# ProPrj___2025-12-12.net
KiCad netlist of a schematic drawn in EasyEDA Pro
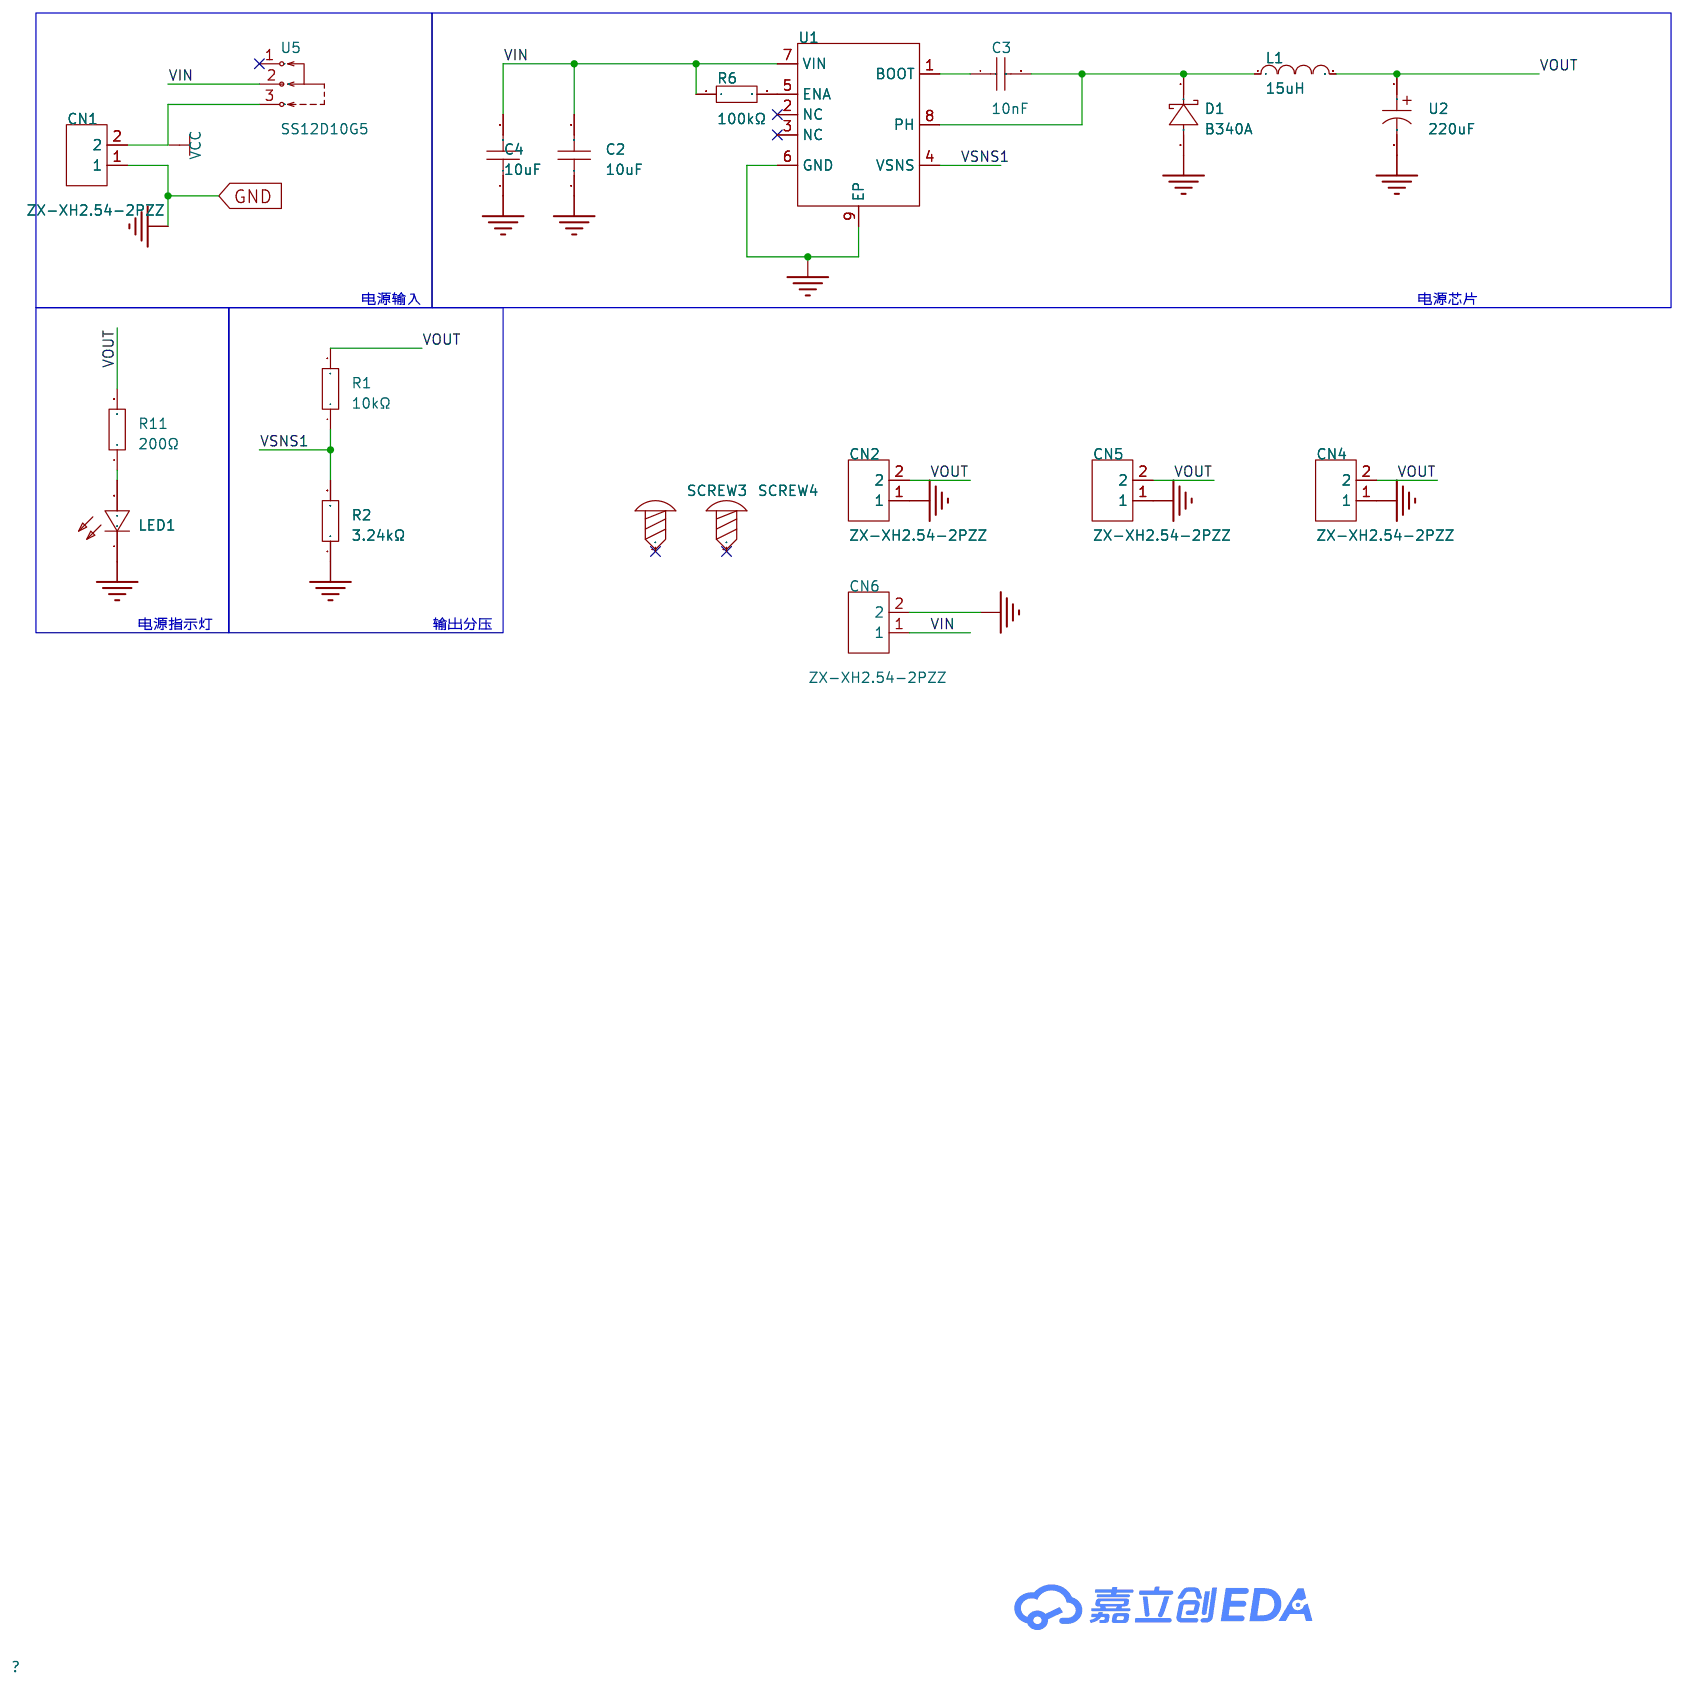
[diagram p0: schematic sheet]

(export (version "E")
  (design (tool "Eeschema 10.0.6"))
  (components
    (comp (ref "C2")
      (value "10uF")
      (footprint "easyedapro:C0603")
      (description "容值:10uF;精度:±20%;额定电压:25V;材质(温度系数):X5R;")
      (fields
        (field (name "Manufacturer Part") "CL10A106MA8NRNC")
        (field (name "Manufacturer") "SAMSUNG(三星)")
      )
      (libsource (lib "easyedapro") (part "CL10A106MA8NRNC"))
    )
    (comp (ref "C3")
      (value "10nF")
      (footprint "easyedapro:C0603")
      (description "容值:10nF;精度:±10%;额定电压:50V;材质(温度系数):X7R;")
      (fields
        (field (name "Manufacturer Part") "CC0603KRX7R9BB103")
        (field (name "Manufacturer") "YAGEO(国巨)")
      )
      (libsource (lib "easyedapro") (part "CC0603KRX7R9BB103"))
    )
    (comp (ref "C4")
      (value "10uF")
      (footprint "easyedapro:C0603")
      (description "容值:10uF;精度:±20%;额定电压:25V;材质(温度系数):X5R;")
      (fields
        (field (name "Manufacturer Part") "CL10A106MA8NRNC")
        (field (name "Manufacturer") "SAMSUNG(三星)")
      )
      (libsource (lib "easyedapro") (part "CL10A106MA8NRNC"))
    )
    (comp (ref "CN1")
      (value "ZX-XH2.54-2PZZ")
      (footprint "easyedapro:CONN-TH_2P-P2.50_HX25003-2A")
      (fields (field (name "Manufacturer") "Megastar(兆星)"))
      (libsource (lib "easyedapro") (part "ZX-XH2.54-2PZZ"))
    )
    (comp (ref "CN2")
      (value "ZX-XH2.54-2PZZ")
      (footprint "easyedapro:CONN-TH_2P-P2.50_HX25003-2A")
      (fields (field (name "Manufacturer") "Megastar(兆星)"))
      (libsource (lib "easyedapro") (part "ZX-XH2.54-2PZZ"))
    )
    (comp (ref "CN4")
      (value "ZX-XH2.54-2PZZ")
      (footprint "easyedapro:CONN-TH_2P-P2.50_HX25003-2A")
      (fields (field (name "Manufacturer") "Megastar(兆星)"))
      (libsource (lib "easyedapro") (part "ZX-XH2.54-2PZZ"))
    )
    (comp (ref "CN5")
      (value "ZX-XH2.54-2PZZ")
      (footprint "easyedapro:CONN-TH_2P-P2.50_HX25003-2A")
      (fields (field (name "Manufacturer") "Megastar(兆星)"))
      (libsource (lib "easyedapro") (part "ZX-XH2.54-2PZZ"))
    )
    (comp (ref "CN6")
      (value "ZX-XH2.54-2PZZ")
      (footprint "easyedapro:CONN-TH_2P-P2.50_HX25003-2A")
      (fields (field (name "Manufacturer") "Megastar(兆星)"))
      (libsource (lib "easyedapro") (part "ZX-XH2.54-2PZZ"))
    )
    (comp (ref "D1")
      (value "B340A")
      (footprint "easyedapro:SMA_L4.3-W2.6-LS5.0-RD")
      (description "正向压降(Vf):550mV@3A;直流反向耐压(Vr):40V;平均整流电流(Io):3A;")
      (fields (field (name "Manufacturer") "FUXINSEMI(富芯森美)"))
      (libsource (lib "easyedapro") (part "B340A_C3018525"))
    )
    (comp (ref "L1")
      (value "15uH")
      (footprint "easyedapro:IND-SMD_L7.0-W6.6_FXL0630")
      (description "电感值:15uH;精度:±20%;额定电流:3A;饱和电流(Isat):4.5A;类型:一体成型电感;")
      (fields (field (name "Manufacturer Part") "FXL0630-150-M") (field (name "Manufacturer") "cjiang(长江微电)"))
      (libsource (lib "easyedapro") (part "FXL0630-150-M"))
    )
    (comp (ref "LED1")
      (value "NCD0603R1")
      (footprint "easyedapro:LED0603-RD_RED")
      (fields (field (name "Manufacturer") "国星光电"))
      (libsource (lib "easyedapro") (part "FC-DA1608HRK-620D"))
    )
    (comp (ref "R1")
      (value "10kΩ")
      (footprint "easyedapro:R0603")
      (description "电阻类型:厚膜电阻;阻值:10kΩ;精度:±1%;功率:100mW;最大工作电压:75V;温度系数:±100ppm/°C;")
      (fields
        (field (name "Manufacturer Part") "0603WAF1002T5E")
        (field (name "Manufacturer") "UNI-ROYAL(厚声)")
      )
      (libsource (lib "easyedapro") (part "0603WAF1002T5E"))
    )
    (comp (ref "R2")
      (value "3.24kΩ")
      (footprint "easyedapro:R0603")
      (description "电阻类型:厚膜电阻;阻值:3.24kΩ;精度:±1%;功率:100mW;最大工作电压:75V;温度系数:±100ppm/°C;")
      (fields
        (field (name "Manufacturer Part") "0603WAF3241T5E")
        (field (name "Manufacturer") "UNI-ROYAL(厚声)")
      )
      (libsource (lib "easyedapro") (part "0603WAF3241T5E"))
    )
    (comp (ref "R6")
      (value "100kΩ")
      (footprint "easyedapro:R0402")
      (description "电阻类型:厚膜电阻;阻值:100kΩ;精度:±1%;功率:62.5mW;最大工作电压:50V;温度系数:±100ppm/°C;")
      (fields (field (name "Manufacturer Part") "RC0402FR-07100KL") (field (name "Manufacturer") "YAGEO(国巨)"))
      (libsource (lib "easyedapro") (part "RC0402FR-07100KL"))
    )
    (comp (ref "R11")
      (value "200Ω")
      (footprint "easyedapro:R0603")
      (description "电阻类型:厚膜电阻;阻值:200Ω;精度:±1%;功率:100mW;最大工作电压:75V;温度系数:±100ppm/°C;")
      (fields
        (field (name "Manufacturer Part") "0603WAF2000T5E")
        (field (name "Manufacturer") "UNI-ROYAL(厚声)")
      )
      (libsource (lib "easyedapro") (part "0603WAF2000T5E"))
    )
    (comp (ref "SCREW3")
      (value "~")
      (footprint "easyedapro:M2螺丝")
      (libsource (lib "easyedapro") (part "螺丝孔"))
    )
    (comp (ref "SCREW4")
      (value "~")
      (footprint "easyedapro:M2螺丝")
      (libsource (lib "easyedapro") (part "螺丝孔"))
    )
    (comp (ref "U1")
      (value "TPS5430DDA")
      (fields (field (name "Manufacturer") "TI(德州仪器)"))
      (libsource (lib "easyedapro") (part "TPS5430DDA"))
    )
    (comp (ref "U2")
      (value "220uF")
      (footprint "easyedapro:CAP-SMD_BD6.3-L6.6-W6.6-LS7.2-FD")
      (description "容值:220uF;精度:±20%;额定电压:25V;纹波电流:165mA@120Hz;等效串联电阻:-;")
      (fields (field (name "Manufacturer Part") "RST220UF25V019") (field (name "Manufacturer") "KNSCHA(科尼盛)"))
      (libsource (lib "easyedapro") (part "RST220UF25V019"))
    )
    (comp (ref "U5")
      (value "SS12D10G5")
      (footprint "easyedapro:SW-TH_SHOU-HAN_SS12D10G4")
      (description "电路结构:单刀双掷;安装方式:直插;额定电流(DC):2A;额定电压(DC):125V;机械寿命:3千次;")
      (fields (field (name "Manufacturer") "SHOU HAN(首韩)"))
      (libsource (lib "easyedapro") (part "SS12D10G5"))
    )
  )
  (nets
    (net (code "1") (name "/VIN") (class "Default")
      (node (ref "C2") (pin "2") (pinfunction "2_2") (pintype "unspecified"))
      (node (ref "C4") (pin "2") (pinfunction "2_2") (pintype "unspecified"))
      (node (ref "CN6") (pin "1") (pinfunction "1_1") (pintype "unspecified"))
      (node (ref "R6") (pin "1") (pinfunction "1_1") (pintype "input"))
      (node (ref "U1") (pin "7") (pinfunction "VIN_7") (pintype "unspecified"))
      (node (ref "U5") (pin "2") (pinfunction "2_2") (pintype "unspecified"))
    )
    (net (code "2") (name "/VOUT") (class "Default")
      (node (ref "CN2") (pin "2") (pinfunction "2_2") (pintype "unspecified"))
      (node (ref "CN4") (pin "2") (pinfunction "2_2") (pintype "unspecified"))
      (node (ref "CN5") (pin "2") (pinfunction "2_2") (pintype "unspecified"))
      (node (ref "L1") (pin "2") (pinfunction "2_2") (pintype "unspecified"))
      (node (ref "R1") (pin "2") (pinfunction "2_2") (pintype "input"))
      (node (ref "R11") (pin "2") (pinfunction "2_2") (pintype "input"))
      (node (ref "U2") (pin "1") (pinfunction "1_1") (pintype "input"))
    )
    (net (code "3") (name "/VSNS1") (class "Default")
      (node (ref "R1") (pin "1") (pinfunction "1_1") (pintype "input"))
      (node (ref "R2") (pin "2") (pinfunction "2_2") (pintype "input"))
      (node (ref "U1") (pin "4") (pinfunction "VSNS_4") (pintype "unspecified"))
    )
    (net (code "4") (name "GND") (class "Default")
      (node (ref "C2") (pin "1") (pinfunction "1_1") (pintype "unspecified"))
      (node (ref "C4") (pin "1") (pinfunction "1_1") (pintype "unspecified"))
      (node (ref "CN1") (pin "1") (pinfunction "1_1") (pintype "unspecified"))
      (node (ref "CN2") (pin "1") (pinfunction "1_1") (pintype "unspecified"))
      (node (ref "CN4") (pin "1") (pinfunction "1_1") (pintype "unspecified"))
      (node (ref "CN5") (pin "1") (pinfunction "1_1") (pintype "unspecified"))
      (node (ref "CN6") (pin "2") (pinfunction "2_2") (pintype "unspecified"))
      (node (ref "D1") (pin "2") (pinfunction "A_2") (pintype "unspecified"))
      (node (ref "LED1") (pin "1") (pinfunction "K_1") (pintype "input"))
      (node (ref "R2") (pin "1") (pinfunction "1_1") (pintype "input"))
      (node (ref "U1") (pin "6") (pinfunction "GND_6") (pintype "unspecified"))
      (node (ref "U1") (pin "9") (pinfunction "EP_9") (pintype "unspecified"))
      (node (ref "U2") (pin "2") (pinfunction "2_2") (pintype "input"))
    )
    (net (code "5") (name "Net-(CN1-Pad2)") (class "Default")
      (node (ref "CN1") (pin "2") (pinfunction "2_2") (pintype "unspecified"))
      (node (ref "U5") (pin "3") (pinfunction "3_3") (pintype "unspecified"))
    )
    (net (code "6") (name "Net-(D1-K)") (class "Default")
      (node (ref "C3") (pin "2") (pinfunction "2_2") (pintype "input"))
      (node (ref "D1") (pin "1") (pinfunction "K_1") (pintype "unspecified"))
      (node (ref "L1") (pin "1") (pinfunction "1_1") (pintype "unspecified"))
      (node (ref "U1") (pin "8") (pinfunction "PH_8") (pintype "unspecified"))
    )
    (net (code "7") (name "Net-(LED1-A)") (class "Default")
      (node (ref "LED1") (pin "2") (pinfunction "A_2") (pintype "input"))
      (node (ref "R11") (pin "1") (pinfunction "1_1") (pintype "input"))
    )
    (net (code "8") (name "Net-(U1-BOOT)") (class "Default")
      (node (ref "C3") (pin "1") (pinfunction "1_1") (pintype "input"))
      (node (ref "U1") (pin "1") (pinfunction "BOOT_1") (pintype "unspecified"))
    )
    (net (code "9") (name "Net-(U1-ENA)") (class "Default")
      (node (ref "R6") (pin "2") (pinfunction "2_2") (pintype "input"))
      (node (ref "U1") (pin "5") (pinfunction "ENA_5") (pintype "unspecified"))
    )
    (net (code "11") (name "unconnected-(SCREW3-Pad1)") (class "Default")
      (node (ref "SCREW3") (pin "1") (pinfunction "1_1") (pintype "input+no_connect"))
    )
    (net (code "12") (name "unconnected-(SCREW4-Pad1)") (class "Default")
      (node (ref "SCREW4") (pin "1") (pinfunction "1_1") (pintype "input+no_connect"))
    )
    (net (code "13") (name "unconnected-(U1-NC-Pad2)") (class "Default")
      (node (ref "U1") (pin "2") (pinfunction "NC_2") (pintype "unspecified+no_connect"))
    )
    (net (code "14") (name "unconnected-(U1-NC-Pad3)") (class "Default")
      (node (ref "U1") (pin "3") (pinfunction "NC_3") (pintype "unspecified+no_connect"))
    )
    (net (code "15") (name "unconnected-(U5-Pad1)") (class "Default")
      (node (ref "U5") (pin "1") (pinfunction "1_1") (pintype "unspecified+no_connect"))
    )
  )
)
